# Main.net
KiCad netlist of a schematic drawn in Altium Designer
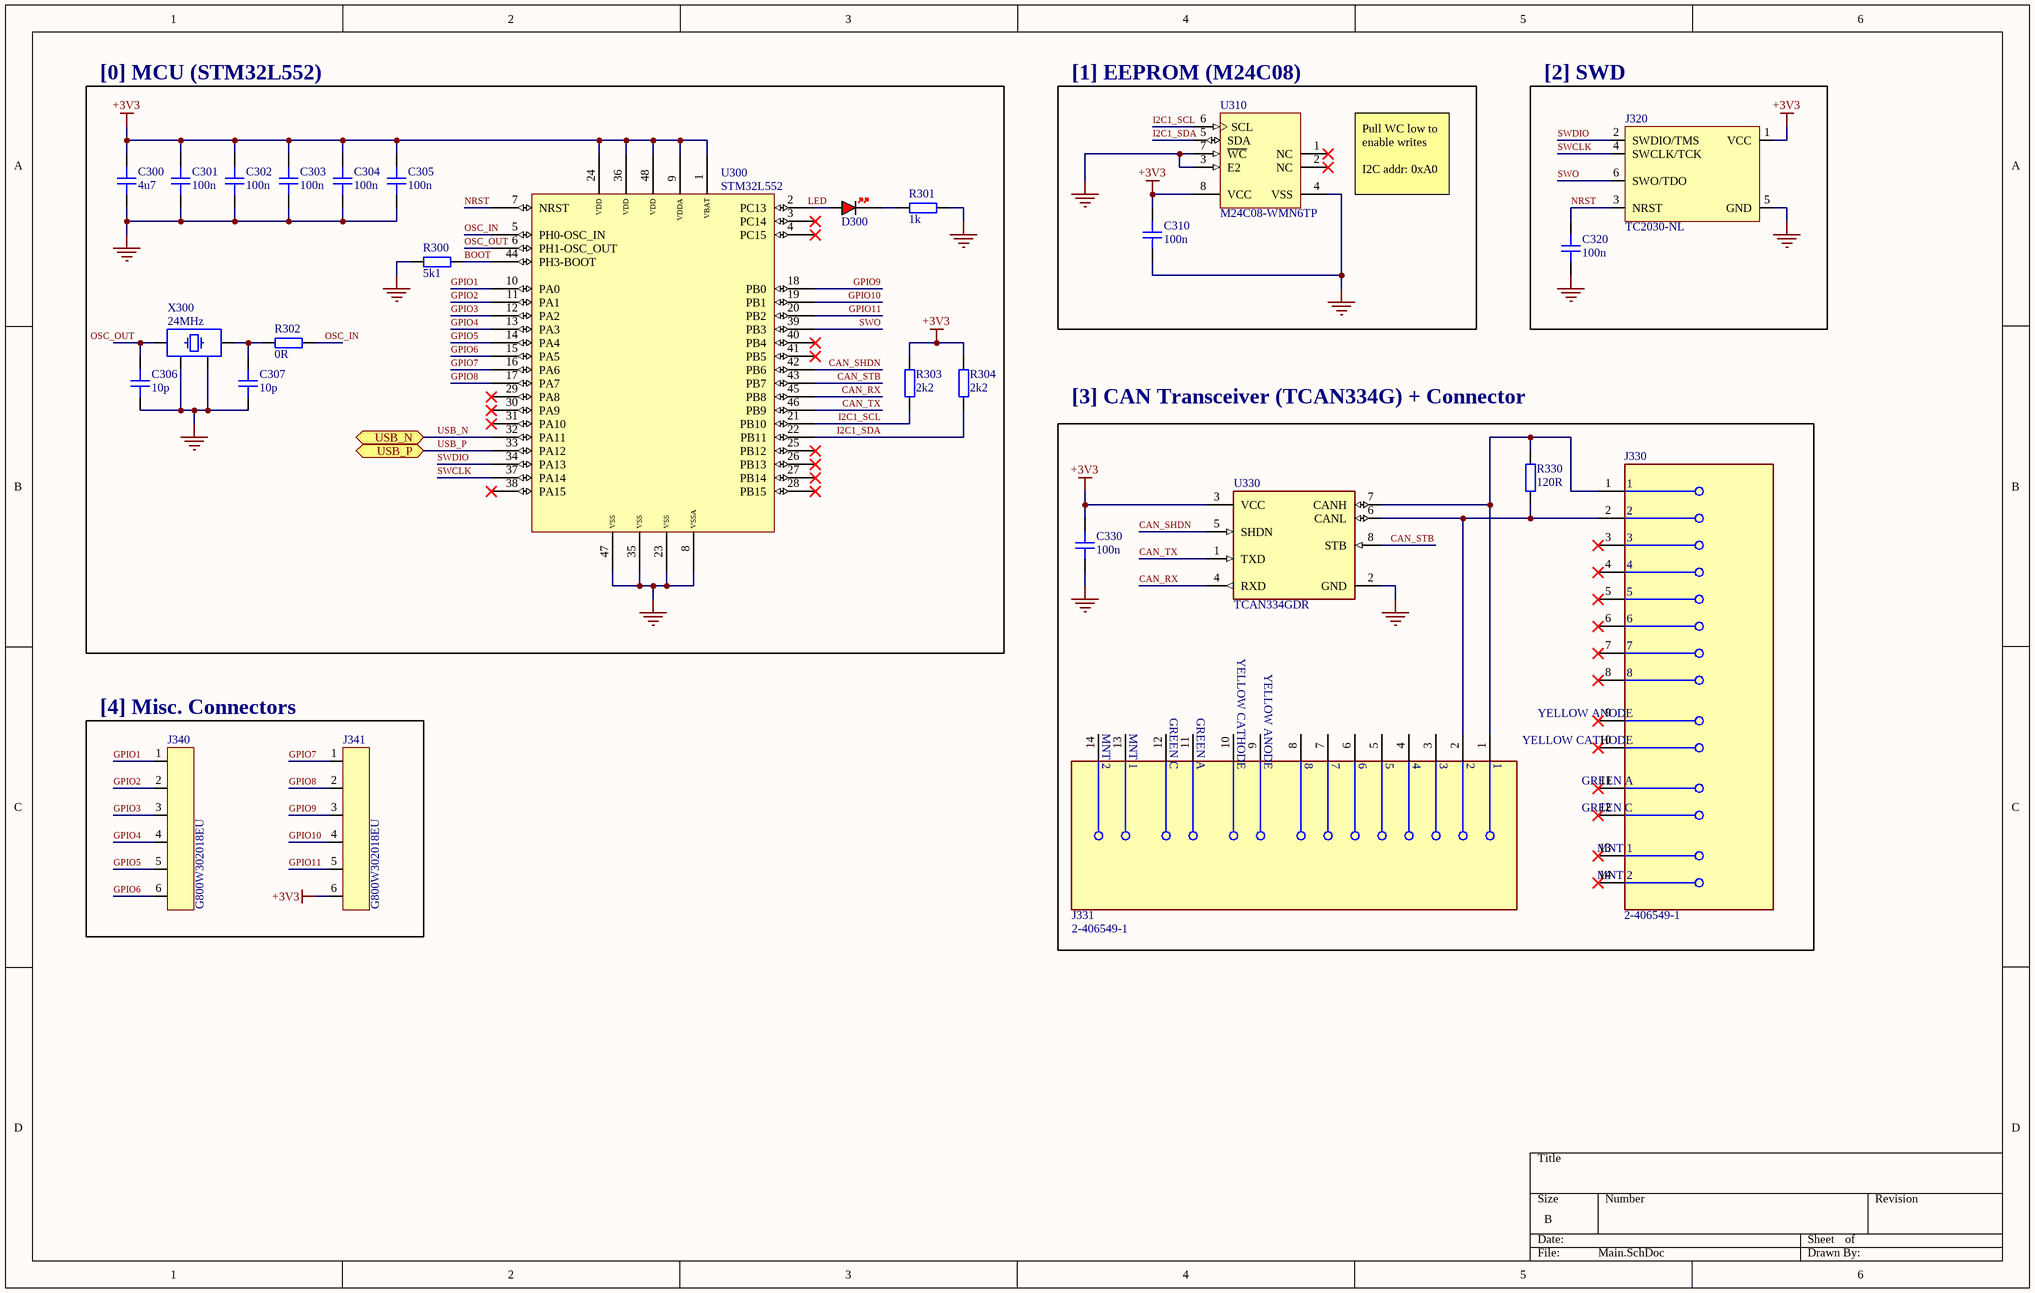
[diagram p0: Main.SchDoc]

(export (version "E")
  (design (tool "Eeschema 10.0.6"))
  (components
    (comp (ref "C300")
      (value "4u7")
      (footprint "CAP_0805")
      (description "Capacitor SMD 0805 16V")
      (libsource (lib "Schematic-Lib-PhilsLab") (part "CAP_0805_16V"))
    )
    (comp (ref "C301")
      (value "100n")
      (footprint "CAP_0603")
      (description "Capacitor SMD 0603 16V")
      (libsource (lib "Schematic-Lib-PhilsLab") (part "CAP_0603_16V"))
    )
    (comp (ref "C302")
      (value "100n")
      (footprint "CAP_0603")
      (description "Capacitor SMD 0603 16V")
      (libsource (lib "Schematic-Lib-PhilsLab") (part "CAP_0603_16V"))
    )
    (comp (ref "C303")
      (value "100n")
      (footprint "CAP_0603")
      (description "Capacitor SMD 0603 16V")
      (libsource (lib "Schematic-Lib-PhilsLab") (part "CAP_0603_16V"))
    )
    (comp (ref "C304")
      (value "100n")
      (footprint "CAP_0603")
      (description "Capacitor SMD 0603 16V")
      (libsource (lib "Schematic-Lib-PhilsLab") (part "CAP_0603_16V"))
    )
    (comp (ref "C305")
      (value "100n")
      (footprint "CAP_0603")
      (description "Capacitor SMD 0603 16V")
      (libsource (lib "Schematic-Lib-PhilsLab") (part "CAP_0603_16V"))
    )
    (comp (ref "C306")
      (value "10p")
      (footprint "CAP_0603")
      (description "Capacitor SMD 0603 16V")
      (libsource (lib "Schematic-Lib-PhilsLab") (part "CAP_0603_16V"))
    )
    (comp (ref "C307")
      (value "10p")
      (footprint "CAP_0603")
      (description "Capacitor SMD 0603 16V")
      (libsource (lib "Schematic-Lib-PhilsLab") (part "CAP_0603_16V"))
    )
    (comp (ref "C310")
      (value "100n")
      (footprint "CAP_0603")
      (description "Capacitor SMD 0603 16V")
      (libsource (lib "Schematic-Lib-PhilsLab") (part "CAP_0603_16V"))
    )
    (comp (ref "C320")
      (value "100n")
      (footprint "CAP_0603")
      (description "Capacitor SMD 0603 16V")
      (libsource (lib "Schematic-Lib-PhilsLab") (part "CAP_0603_16V"))
    )
    (comp (ref "C330")
      (value "100n")
      (footprint "CAP_0603")
      (description "Capacitor SMD 0603 16V")
      (libsource (lib "Schematic-Lib-PhilsLab") (part "CAP_0603_16V"))
    )
    (comp (ref "D300")
      (value "RED")
      (footprint "LED_0603_RED")
      (description "LED 0603 RED SMD")
      (libsource (lib "Schematic-Lib-PhilsLab") (part "LED_0603_RED"))
    )
    (comp (ref "J320")
      (value "TC2030-NL")
      (footprint "TC2030-NL-FP")
      (description "Tag-Connect No-Solder SWD Debug Connector (No Legs) DO NOT PLACE")
      (fields
        (field (name "MANUFACTURER") "Tag-Connect")
        (field (name "MANUFACTURER PART NUMBER") "TC2030-NL-FP")
      )
      (libsource (lib "Schematic-Lib-PhilsLab") (part "TC2030-NL"))
    )
    (comp (ref "J330")
      (value "2-406549-1")
      (footprint "FP-2-406549-1-MFG")
      (description "CONN MOD JACK 8P8C R/A SHIELDED")
      (libsource (lib "") (part "5df2851a84d4daa1b10777dbcf9e12f_1"))
    )
    (comp (ref "J331")
      (value "2-406549-1")
      (footprint "FP-2-406549-1-MFG")
      (description "CONN MOD JACK 8P8C R/A SHIELDED")
      (libsource (lib "Altium Content Vault") (part "5df2851a84d4daa1b10777dbcf9e12f"))
    )
    (comp (ref "J340")
      (value "G800W302018EU")
      (footprint "G800W302018EU")
      (description "Pin Header 6 Position 2.54mm Pitch")
      (fields (field (name "MANUFACTURER") "Amphenol"))
      (libsource (lib "Schematic-Lib-PhilsLab") (part "G800W302018EU"))
    )
    (comp (ref "J341")
      (value "G800W302018EU")
      (footprint "G800W302018EU")
      (description "Pin Header 6 Position 2.54mm Pitch")
      (fields (field (name "MANUFACTURER") "Amphenol"))
      (libsource (lib "Schematic-Lib-PhilsLab") (part "G800W302018EU"))
    )
    (comp (ref "R300")
      (value "5k1")
      (footprint "RES_0603")
      (description "Resistor SMD 0603")
      (libsource (lib "Schematic-Lib-PhilsLab") (part "RES_0603"))
    )
    (comp (ref "R301")
      (value "1k")
      (footprint "RES_0603")
      (description "Resistor SMD 0603")
      (libsource (lib "Schematic-Lib-PhilsLab") (part "RES_0603"))
    )
    (comp (ref "R302")
      (value "0R")
      (footprint "RES_0603")
      (description "Resistor SMD 0603")
      (libsource (lib "Schematic-Lib-PhilsLab") (part "RES_0603"))
    )
    (comp (ref "R303")
      (value "2k2")
      (footprint "RES_0603")
      (description "Resistor SMD 0603")
      (libsource (lib "Schematic-Lib-PhilsLab") (part "RES_0603"))
    )
    (comp (ref "R304")
      (value "2k2")
      (footprint "RES_0603")
      (description "Resistor SMD 0603")
      (libsource (lib "Schematic-Lib-PhilsLab") (part "RES_0603"))
    )
    (comp (ref "R330")
      (value "120R")
      (footprint "RES_0603")
      (description "Resistor SMD 0603")
      (libsource (lib "Schematic-Lib-PhilsLab") (part "RES_0603"))
    )
    (comp (ref "U300")
      (value "STM32L552")
      (footprint "LQFP48")
      (description "STM32L552 MCU LQFP-48")
      (libsource (lib "Library") (part "STM32L552"))
    )
    (comp (ref "U310")
      (value "M24C08-WMN6TP")
      (footprint "STM-SOIC-8_L")
      (description "I2C Bus EEPROM, 8 Kbits, 2.5 to 5.5 V, -40 to 85 degC, 8-Pin SOIC, RoHS, Tape and Reel")
      (fields (field (name "MANUFACTURER") "STMicroelectronics"))
      (libsource (lib "Altium Content Vault") (part "STM-M24C08-SO-8"))
    )
    (comp (ref "U330")
      (value "TCAN334GDR")
      (footprint "FP-D0008A-IPC_B")
      (description "IC TRANSCEIVER 1/1 8SOIC")
      (libsource (lib "Altium Content Vault") (part "5621f34e3963f16c2984a53bd88c479"))
    )
    (comp (ref "X300")
      (value "24MHz")
      (footprint "XTAL_3225")
      (description "Crystal SMD 24MHz 10PPM 7pF 3225")
      (fields (field (name "MANUFACTURER") "Epson"))
      (libsource (lib "Schematic-Lib-PhilsLab") (part "TSX-3225_24.0000MF15X-AC"))
    )
  )
  (nets
    (net (code "1") (name "+3V3") (class "Default")
      (node (ref "C300") (pin "2") (pinfunction "2_2") (pintype "passive"))
      (node (ref "C301") (pin "2") (pinfunction "2_2") (pintype "passive"))
      (node (ref "C302") (pin "2") (pinfunction "2_2") (pintype "passive"))
      (node (ref "C303") (pin "2") (pinfunction "2_2") (pintype "passive"))
      (node (ref "C304") (pin "2") (pinfunction "2_2") (pintype "passive"))
      (node (ref "C305") (pin "2") (pinfunction "2_2") (pintype "passive"))
      (node (ref "C310") (pin "1") (pinfunction "1_1") (pintype "passive"))
      (node (ref "C330") (pin "2") (pinfunction "2_2") (pintype "passive"))
      (node (ref "J320") (pin "1") (pinfunction "VCC_1") (pintype "passive"))
      (node (ref "J341") (pin "6") (pinfunction "6_6") (pintype "passive"))
      (node (ref "R303") (pin "2") (pinfunction "2_2") (pintype "passive"))
      (node (ref "R304") (pin "2") (pinfunction "2_2") (pintype "passive"))
      (node (ref "U300") (pin "1") (pinfunction "VBAT_1") (pintype "passive"))
      (node (ref "U300") (pin "24") (pinfunction "VDD_24") (pintype "passive"))
      (node (ref "U300") (pin "36") (pinfunction "VDD_36") (pintype "passive"))
      (node (ref "U300") (pin "48") (pinfunction "VDD_48") (pintype "passive"))
      (node (ref "U300") (pin "9") (pinfunction "VDDA_9") (pintype "passive"))
      (node (ref "U310") (pin "8") (pinfunction "VCC_8") (pintype "power_in"))
      (node (ref "U330") (pin "3") (pinfunction "VCC_3") (pintype "power_in"))
    )
    (net (code "2") (name "/BOOT") (class "Default")
      (node (ref "R300") (pin "1") (pinfunction "1_1") (pintype "passive"))
      (node (ref "U300") (pin "44") (pinfunction "PH3-BOOT_44") (pintype "bidirectional"))
    )
    (net (code "3") (name "/CAN_RX") (class "Default")
      (node (ref "U300") (pin "45") (pinfunction "PB8_45") (pintype "bidirectional"))
      (node (ref "U330") (pin "4") (pinfunction "RXD_4") (pintype "output"))
    )
    (net (code "4") (name "/CAN_SHDN") (class "Default")
      (node (ref "U300") (pin "42") (pinfunction "PB6_42") (pintype "bidirectional"))
      (node (ref "U330") (pin "5") (pinfunction "SHDN_5") (pintype "input"))
    )
    (net (code "5") (name "/CAN_STB") (class "Default")
      (node (ref "U300") (pin "43") (pinfunction "PB7_43") (pintype "bidirectional"))
      (node (ref "U330") (pin "8") (pinfunction "STB_8") (pintype "input"))
    )
    (net (code "6") (name "/CAN_TX") (class "Default")
      (node (ref "U300") (pin "46") (pinfunction "PB9_46") (pintype "bidirectional"))
      (node (ref "U330") (pin "1") (pinfunction "TXD_1") (pintype "input"))
    )
    (net (code "7") (name "/GPIO1") (class "Default")
      (node (ref "J340") (pin "1") (pinfunction "1_1") (pintype "passive"))
      (node (ref "U300") (pin "10") (pinfunction "PA0_10") (pintype "bidirectional"))
    )
    (net (code "8") (name "/GPIO2") (class "Default")
      (node (ref "J340") (pin "2") (pinfunction "2_2") (pintype "passive"))
      (node (ref "U300") (pin "11") (pinfunction "PA1_11") (pintype "bidirectional"))
    )
    (net (code "9") (name "/GPIO3") (class "Default")
      (node (ref "J340") (pin "3") (pinfunction "3_3") (pintype "passive"))
      (node (ref "U300") (pin "12") (pinfunction "PA2_12") (pintype "bidirectional"))
    )
    (net (code "10") (name "/GPIO4") (class "Default")
      (node (ref "J340") (pin "4") (pinfunction "4_4") (pintype "passive"))
      (node (ref "U300") (pin "13") (pinfunction "PA3_13") (pintype "bidirectional"))
    )
    (net (code "11") (name "/GPIO5") (class "Default")
      (node (ref "J340") (pin "5") (pinfunction "5_5") (pintype "passive"))
      (node (ref "U300") (pin "14") (pinfunction "PA4_14") (pintype "bidirectional"))
    )
    (net (code "12") (name "/GPIO6") (class "Default")
      (node (ref "J340") (pin "6") (pinfunction "6_6") (pintype "passive"))
      (node (ref "U300") (pin "15") (pinfunction "PA5_15") (pintype "bidirectional"))
    )
    (net (code "13") (name "/GPIO7") (class "Default")
      (node (ref "J341") (pin "1") (pinfunction "1_1") (pintype "passive"))
      (node (ref "U300") (pin "16") (pinfunction "PA6_16") (pintype "bidirectional"))
    )
    (net (code "14") (name "/GPIO8") (class "Default")
      (node (ref "J341") (pin "2") (pinfunction "2_2") (pintype "passive"))
      (node (ref "U300") (pin "17") (pinfunction "PA7_17") (pintype "bidirectional"))
    )
    (net (code "15") (name "/GPIO9") (class "Default")
      (node (ref "J341") (pin "3") (pinfunction "3_3") (pintype "passive"))
      (node (ref "U300") (pin "18") (pinfunction "PB0_18") (pintype "bidirectional"))
    )
    (net (code "16") (name "/GPIO10") (class "Default")
      (node (ref "J341") (pin "4") (pinfunction "4_4") (pintype "passive"))
      (node (ref "U300") (pin "19") (pinfunction "PB1_19") (pintype "bidirectional"))
    )
    (net (code "17") (name "/GPIO11") (class "Default")
      (node (ref "J341") (pin "5") (pinfunction "5_5") (pintype "passive"))
      (node (ref "U300") (pin "20") (pinfunction "PB2_20") (pintype "bidirectional"))
    )
    (net (code "18") (name "/I2C1_SCL") (class "Default")
      (node (ref "R303") (pin "1") (pinfunction "1_1") (pintype "passive"))
      (node (ref "U300") (pin "21") (pinfunction "PB10_21") (pintype "bidirectional"))
      (node (ref "U310") (pin "6") (pinfunction "SCL_6") (pintype "input"))
    )
    (net (code "19") (name "/I2C1_SDA") (class "Default")
      (node (ref "R304") (pin "1") (pinfunction "1_1") (pintype "passive"))
      (node (ref "U300") (pin "22") (pinfunction "PB11_22") (pintype "bidirectional"))
      (node (ref "U310") (pin "5") (pinfunction "SDA_5") (pintype "bidirectional"))
    )
    (net (code "20") (name "/LED") (class "Default")
      (node (ref "D300") (pin "A") (pinfunction "A_A") (pintype "passive"))
      (node (ref "U300") (pin "2") (pinfunction "PC13_2") (pintype "bidirectional"))
    )
    (net (code "21") (name "/NRST") (class "Default")
      (node (ref "C320") (pin "2") (pinfunction "2_2") (pintype "passive"))
      (node (ref "J320") (pin "3") (pinfunction "NRST_3") (pintype "passive"))
      (node (ref "U300") (pin "7") (pinfunction "NRST_7") (pintype "bidirectional"))
    )
    (net (code "22") (name "/OSC_IN") (class "Default")
      (node (ref "R302") (pin "1") (pinfunction "1_1") (pintype "passive"))
      (node (ref "U300") (pin "5") (pinfunction "PH0-OSC_IN_5") (pintype "bidirectional"))
    )
    (net (code "23") (name "/OSC_OUT") (class "Default")
      (node (ref "C306") (pin "1") (pinfunction "1_1") (pintype "passive"))
      (node (ref "U300") (pin "6") (pinfunction "PH1-OSC_OUT_6") (pintype "bidirectional"))
      (node (ref "X300") (pin "1") (pinfunction "1_1") (pintype "passive"))
    )
    (net (code "24") (name "/SWCLK") (class "Default")
      (node (ref "J320") (pin "4") (pinfunction "SWCLK/TCK_4") (pintype "passive"))
      (node (ref "U300") (pin "37") (pinfunction "PA14_37") (pintype "bidirectional"))
    )
    (net (code "25") (name "/SWDIO") (class "Default")
      (node (ref "J320") (pin "2") (pinfunction "SWDIO/TMS_2") (pintype "passive"))
      (node (ref "U300") (pin "34") (pinfunction "PA13_34") (pintype "bidirectional"))
    )
    (net (code "26") (name "/SWO") (class "Default")
      (node (ref "J320") (pin "6") (pinfunction "SWO/TDO_6") (pintype "passive"))
      (node (ref "U300") (pin "39") (pinfunction "PB3_39") (pintype "bidirectional"))
    )
    (net (code "27") (name "/USB_N") (class "Default")
      (node (ref "U300") (pin "32") (pinfunction "PA11_32") (pintype "bidirectional"))
    )
    (net (code "28") (name "/USB_P") (class "Default")
      (node (ref "U300") (pin "33") (pinfunction "PA12_33") (pintype "bidirectional"))
    )
    (net (code "29") (name "GND") (class "Default")
      (node (ref "C300") (pin "1") (pinfunction "1_1") (pintype "passive"))
      (node (ref "C301") (pin "1") (pinfunction "1_1") (pintype "passive"))
      (node (ref "C302") (pin "1") (pinfunction "1_1") (pintype "passive"))
      (node (ref "C303") (pin "1") (pinfunction "1_1") (pintype "passive"))
      (node (ref "C304") (pin "1") (pinfunction "1_1") (pintype "passive"))
      (node (ref "C305") (pin "1") (pinfunction "1_1") (pintype "passive"))
      (node (ref "C306") (pin "2") (pinfunction "2_2") (pintype "passive"))
      (node (ref "C307") (pin "1") (pinfunction "1_1") (pintype "passive"))
      (node (ref "C310") (pin "2") (pinfunction "2_2") (pintype "passive"))
      (node (ref "C320") (pin "1") (pinfunction "1_1") (pintype "passive"))
      (node (ref "C330") (pin "1") (pinfunction "1_1") (pintype "passive"))
      (node (ref "J320") (pin "5") (pinfunction "GND_5") (pintype "passive"))
      (node (ref "R300") (pin "2") (pinfunction "2_2") (pintype "passive"))
      (node (ref "R301") (pin "2") (pinfunction "2_2") (pintype "passive"))
      (node (ref "U300") (pin "23") (pinfunction "VSS_23") (pintype "power_in"))
      (node (ref "U300") (pin "35") (pinfunction "VSS_35") (pintype "power_in"))
      (node (ref "U300") (pin "47") (pinfunction "VSS_47") (pintype "power_in"))
      (node (ref "U300") (pin "8") (pinfunction "VSSA_8") (pintype "power_in"))
      (node (ref "U310") (pin "3") (pinfunction "E2_3") (pintype "input"))
      (node (ref "U310") (pin "4") (pinfunction "VSS_4") (pintype "power_in"))
      (node (ref "U310") (pin "7") (pinfunction "~{WC}_7") (pintype "input"))
      (node (ref "U330") (pin "2") (pinfunction "GND_2") (pintype "power_in"))
      (node (ref "X300") (pin "2") (pinfunction "2_2") (pintype "passive"))
      (node (ref "X300") (pin "4") (pinfunction "4_4") (pintype "passive"))
    )
    (net (code "30") (name "Net-(C307-Pad2)") (class "Default")
      (node (ref "C307") (pin "2") (pinfunction "2_2") (pintype "passive"))
      (node (ref "R302") (pin "2") (pinfunction "2_2") (pintype "passive"))
      (node (ref "X300") (pin "3") (pinfunction "3_3") (pintype "passive"))
    )
    (net (code "31") (name "Net-(D300-PadK)") (class "Default")
      (node (ref "D300") (pin "K") (pinfunction "K_K") (pintype "passive"))
      (node (ref "R301") (pin "1") (pinfunction "1_1") (pintype "passive"))
    )
    (net (code "32") (name "Net-(U330-CANH)") (class "Default")
      (node (ref "J330") (pin "1") (pinfunction "1_1") (pintype "passive"))
      (node (ref "J331") (pin "1") (pinfunction "1_1") (pintype "passive"))
      (node (ref "R330") (pin "2") (pinfunction "2_2") (pintype "passive"))
      (node (ref "U330") (pin "7") (pinfunction "CANH_7") (pintype "bidirectional"))
    )
    (net (code "33") (name "Net-(U330-CANL)") (class "Default")
      (node (ref "J330") (pin "2") (pinfunction "2_2") (pintype "passive"))
      (node (ref "J331") (pin "2") (pinfunction "2_2") (pintype "passive"))
      (node (ref "R330") (pin "1") (pinfunction "1_1") (pintype "passive"))
      (node (ref "U330") (pin "6") (pinfunction "CANL_6") (pintype "bidirectional"))
    )
    (net (code "34") (name "unconnected-(J330-GREEN_A-Pad11)") (class "Default")
      (node (ref "J330") (pin "11") (pinfunction "GREEN_A_11") (pintype "passive+no_connect"))
    )
    (net (code "35") (name "unconnected-(J330-GREEN_C-Pad12)") (class "Default")
      (node (ref "J330") (pin "12") (pinfunction "GREEN_C_12") (pintype "passive+no_connect"))
    )
    (net (code "36") (name "unconnected-(J330-MNT_1-Pad13)") (class "Default")
      (node (ref "J330") (pin "13") (pinfunction "MNT_1_13") (pintype "passive+no_connect"))
    )
    (net (code "37") (name "unconnected-(J330-MNT_2-Pad14)") (class "Default")
      (node (ref "J330") (pin "14") (pinfunction "MNT_2_14") (pintype "passive+no_connect"))
    )
    (net (code "38") (name "unconnected-(J330-Pad3)") (class "Default")
      (node (ref "J330") (pin "3") (pinfunction "3_3") (pintype "passive+no_connect"))
    )
    (net (code "39") (name "unconnected-(J330-Pad4)") (class "Default")
      (node (ref "J330") (pin "4") (pinfunction "4_4") (pintype "passive+no_connect"))
    )
    (net (code "40") (name "unconnected-(J330-Pad5)") (class "Default")
      (node (ref "J330") (pin "5") (pinfunction "5_5") (pintype "passive+no_connect"))
    )
    (net (code "41") (name "unconnected-(J330-Pad6)") (class "Default")
      (node (ref "J330") (pin "6") (pinfunction "6_6") (pintype "passive+no_connect"))
    )
    (net (code "42") (name "unconnected-(J330-Pad7)") (class "Default")
      (node (ref "J330") (pin "7") (pinfunction "7_7") (pintype "passive+no_connect"))
    )
    (net (code "43") (name "unconnected-(J330-Pad8)") (class "Default")
      (node (ref "J330") (pin "8") (pinfunction "8_8") (pintype "passive+no_connect"))
    )
    (net (code "44") (name "unconnected-(J330-YELLOW_ANODE-Pad9)") (class "Default")
      (node (ref "J330") (pin "9") (pinfunction "YELLOW_ANODE_9") (pintype "passive+no_connect"))
    )
    (net (code "45") (name "unconnected-(J330-YELLOW_CATHODE-Pad10)") (class "Default")
      (node (ref "J330") (pin "10") (pinfunction "YELLOW_CATHODE_10") (pintype "passive+no_connect"))
    )
    (net (code "46") (name "unconnected-(J331-GREEN_A-Pad11)") (class "Default")
      (node (ref "J331") (pin "11") (pinfunction "GREEN_A_11") (pintype "passive"))
    )
    (net (code "47") (name "unconnected-(J331-GREEN_C-Pad12)") (class "Default")
      (node (ref "J331") (pin "12") (pinfunction "GREEN_C_12") (pintype "passive"))
    )
    (net (code "48") (name "unconnected-(J331-MNT_1-Pad13)") (class "Default")
      (node (ref "J331") (pin "13") (pinfunction "MNT_1_13") (pintype "passive"))
    )
    (net (code "49") (name "unconnected-(J331-MNT_2-Pad14)") (class "Default")
      (node (ref "J331") (pin "14") (pinfunction "MNT_2_14") (pintype "passive"))
    )
    (net (code "50") (name "unconnected-(J331-Pad3)") (class "Default")
      (node (ref "J331") (pin "3") (pinfunction "3_3") (pintype "passive"))
    )
    (net (code "51") (name "unconnected-(J331-Pad4)") (class "Default")
      (node (ref "J331") (pin "4") (pinfunction "4_4") (pintype "passive"))
    )
    (net (code "52") (name "unconnected-(J331-Pad5)") (class "Default")
      (node (ref "J331") (pin "5") (pinfunction "5_5") (pintype "passive"))
    )
    (net (code "53") (name "unconnected-(J331-Pad6)") (class "Default")
      (node (ref "J331") (pin "6") (pinfunction "6_6") (pintype "passive"))
    )
    (net (code "54") (name "unconnected-(J331-Pad7)") (class "Default")
      (node (ref "J331") (pin "7") (pinfunction "7_7") (pintype "passive"))
    )
    (net (code "55") (name "unconnected-(J331-Pad8)") (class "Default")
      (node (ref "J331") (pin "8") (pinfunction "8_8") (pintype "passive"))
    )
    (net (code "56") (name "unconnected-(J331-YELLOW_ANODE-Pad9)") (class "Default")
      (node (ref "J331") (pin "9") (pinfunction "YELLOW_ANODE_9") (pintype "passive"))
    )
    (net (code "57") (name "unconnected-(J331-YELLOW_CATHODE-Pad10)") (class "Default")
      (node (ref "J331") (pin "10") (pinfunction "YELLOW_CATHODE_10") (pintype "passive"))
    )
    (net (code "58") (name "unconnected-(U300-PA8-Pad29)") (class "Default")
      (node (ref "U300") (pin "29") (pinfunction "PA8_29") (pintype "bidirectional+no_connect"))
    )
    (net (code "59") (name "unconnected-(U300-PA9-Pad30)") (class "Default")
      (node (ref "U300") (pin "30") (pinfunction "PA9_30") (pintype "bidirectional+no_connect"))
    )
    (net (code "60") (name "unconnected-(U300-PA10-Pad31)") (class "Default")
      (node (ref "U300") (pin "31") (pinfunction "PA10_31") (pintype "bidirectional+no_connect"))
    )
    (net (code "61") (name "unconnected-(U300-PA15-Pad38)") (class "Default")
      (node (ref "U300") (pin "38") (pinfunction "PA15_38") (pintype "bidirectional+no_connect"))
    )
    (net (code "62") (name "unconnected-(U300-PB4-Pad40)") (class "Default")
      (node (ref "U300") (pin "40") (pinfunction "PB4_40") (pintype "bidirectional+no_connect"))
    )
    (net (code "63") (name "unconnected-(U300-PB5-Pad41)") (class "Default")
      (node (ref "U300") (pin "41") (pinfunction "PB5_41") (pintype "bidirectional+no_connect"))
    )
    (net (code "64") (name "unconnected-(U300-PB12-Pad25)") (class "Default")
      (node (ref "U300") (pin "25") (pinfunction "PB12_25") (pintype "bidirectional+no_connect"))
    )
    (net (code "65") (name "unconnected-(U300-PB13-Pad26)") (class "Default")
      (node (ref "U300") (pin "26") (pinfunction "PB13_26") (pintype "bidirectional+no_connect"))
    )
    (net (code "66") (name "unconnected-(U300-PB14-Pad27)") (class "Default")
      (node (ref "U300") (pin "27") (pinfunction "PB14_27") (pintype "bidirectional+no_connect"))
    )
    (net (code "67") (name "unconnected-(U300-PB15-Pad28)") (class "Default")
      (node (ref "U300") (pin "28") (pinfunction "PB15_28") (pintype "bidirectional+no_connect"))
    )
    (net (code "68") (name "unconnected-(U300-PC14-Pad3)") (class "Default")
      (node (ref "U300") (pin "3") (pinfunction "PC14_3") (pintype "bidirectional+no_connect"))
    )
    (net (code "69") (name "unconnected-(U300-PC15-Pad4)") (class "Default")
      (node (ref "U300") (pin "4") (pinfunction "PC15_4") (pintype "bidirectional+no_connect"))
    )
    (net (code "70") (name "unconnected-(U310-NC-Pad1)") (class "Default")
      (node (ref "U310") (pin "1") (pinfunction "NC_1") (pintype "passive+no_connect"))
    )
    (net (code "71") (name "unconnected-(U310-NC-Pad2)") (class "Default")
      (node (ref "U310") (pin "2") (pinfunction "NC_2") (pintype "passive+no_connect"))
    )
  )
)
